# Heaters.net
KiCad netlist of a schematic drawn in Altium Designer
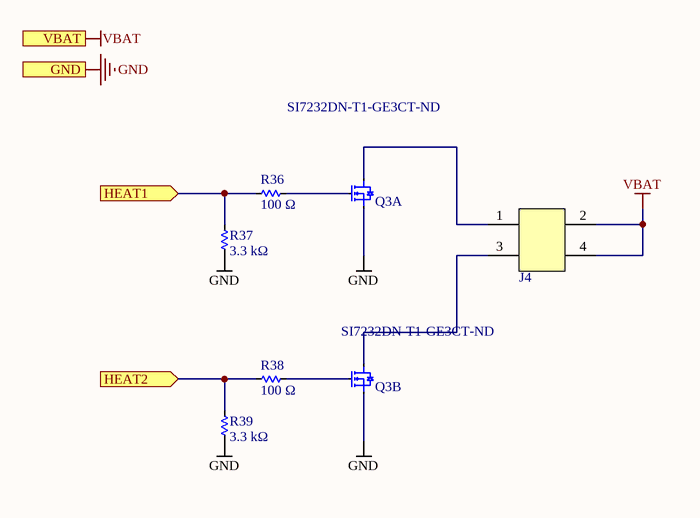
[diagram p0: Heaters.SchDoc]

(export (version "E")
  (design (tool "Eeschema 10.0.6"))
  (components
    (comp (ref "J4")
      (value "CONN_2X2_Harwin_M80-5T104")
      (footprint "Harwin M80-5T104")
      (libsource (lib "SSI") (part "CONN_2X2_Harwin_M80-5T104"))
    )
    (comp (ref "Q3")
      (value "NFET_SI7232DN")
      (footprint "POWERPAK_1212-8_DUAL")
      (description "MOSFET 2N-CH 20V 25A PPAK 1212-8")
      (fields
        (field (name "SUPPLIER PART NUMBER 1") "SI7232DN-T1-GE3CT-ND")
        (field (name "MANUFACTURER") "Vishay Siliconix")
        (field (name "MANUFACTURER PART NUMBER") "SI7232DN-T1-GE3")
      )
      (libsource (lib "SSI") (part "NFET_SI7232DN"))
    )
    (comp (ref "R36")
      (value "__template_resistor")
      (footprint "R0603")
      (description "RES SMD 100 OHM 1% 1/10W 0603")
      (fields
        (field (name "MANUFACTURER PART NUMBER") "RC0603FR-07100RL")
        (field (name "MANUFACTURER") "Yageo")
        (field (name "RESISTANCE") "100 Ω")
      )
      (libsource (lib "passives") (part "__template_resistor"))
    )
    (comp (ref "R37")
      (value "__template_resistor")
      (footprint "R0603")
      (description "RES SMD 3.3K OHM 1% 1/10W 0603")
      (fields
        (field (name "MANUFACTURER PART NUMBER") "RC0603FR-073K3L")
        (field (name "MANUFACTURER") "Yageo")
        (field (name "RESISTANCE") "3.3 kΩ")
      )
      (libsource (lib "passives") (part "__template_resistor"))
    )
    (comp (ref "R38")
      (value "__template_resistor")
      (footprint "R0603")
      (description "RES SMD 100 OHM 1% 1/10W 0603")
      (fields
        (field (name "MANUFACTURER PART NUMBER") "RC0603FR-07100RL")
        (field (name "MANUFACTURER") "Yageo")
        (field (name "RESISTANCE") "100 Ω")
      )
      (libsource (lib "passives") (part "__template_resistor"))
    )
    (comp (ref "R39")
      (value "__template_resistor")
      (footprint "R0603")
      (description "RES SMD 3.3K OHM 1% 1/10W 0603")
      (fields
        (field (name "MANUFACTURER PART NUMBER") "RC0603FR-073K3L")
        (field (name "MANUFACTURER") "Yageo")
        (field (name "RESISTANCE") "3.3 kΩ")
      )
      (libsource (lib "passives") (part "__template_resistor"))
    )
  )
  (nets
    (net (code "1") (name "/HEAT1") (class "Default")
      (node (ref "R36") (pin "1") (pintype "passive"))
      (node (ref "R37") (pin "2") (pintype "passive"))
    )
    (net (code "2") (name "/HEAT2") (class "Default")
      (node (ref "R38") (pin "1") (pintype "passive"))
      (node (ref "R39") (pin "2") (pintype "passive"))
    )
    (net (code "3") (name "GND") (class "Default")
      (node (ref "Q3") (pin "1") (pintype "passive"))
      (node (ref "Q3") (pin "3") (pintype "passive"))
      (node (ref "R37") (pin "1") (pintype "passive"))
      (node (ref "R39") (pin "1") (pintype "passive"))
    )
    (net (code "4") (name "Net-(J4-Pad1)") (class "Default")
      (node (ref "J4") (pin "1") (pinfunction "1_1") (pintype "passive"))
      (node (ref "Q3") (pin "7") (pintype "passive"))
    )
    (net (code "5") (name "Net-(J4-Pad3)") (class "Default")
      (node (ref "J4") (pin "3") (pinfunction "3_3") (pintype "passive"))
      (node (ref "Q3") (pin "5") (pintype "passive"))
    )
    (net (code "6") (name "Net-(Q3-Pad2)") (class "Default")
      (node (ref "Q3") (pin "2") (pintype "passive"))
      (node (ref "R36") (pin "2") (pintype "passive"))
    )
    (net (code "7") (name "Net-(Q3-Pad4)") (class "Default")
      (node (ref "Q3") (pin "4") (pintype "passive"))
      (node (ref "R38") (pin "2") (pintype "passive"))
    )
    (net (code "8") (name "VBAT") (class "Default")
      (node (ref "J4") (pin "2") (pinfunction "2_2") (pintype "passive"))
      (node (ref "J4") (pin "4") (pinfunction "4_4") (pintype "passive"))
    )
  )
)
